# reefpi_pico_io.net
KiCad netlist of a schematic drawn in Altium Designer
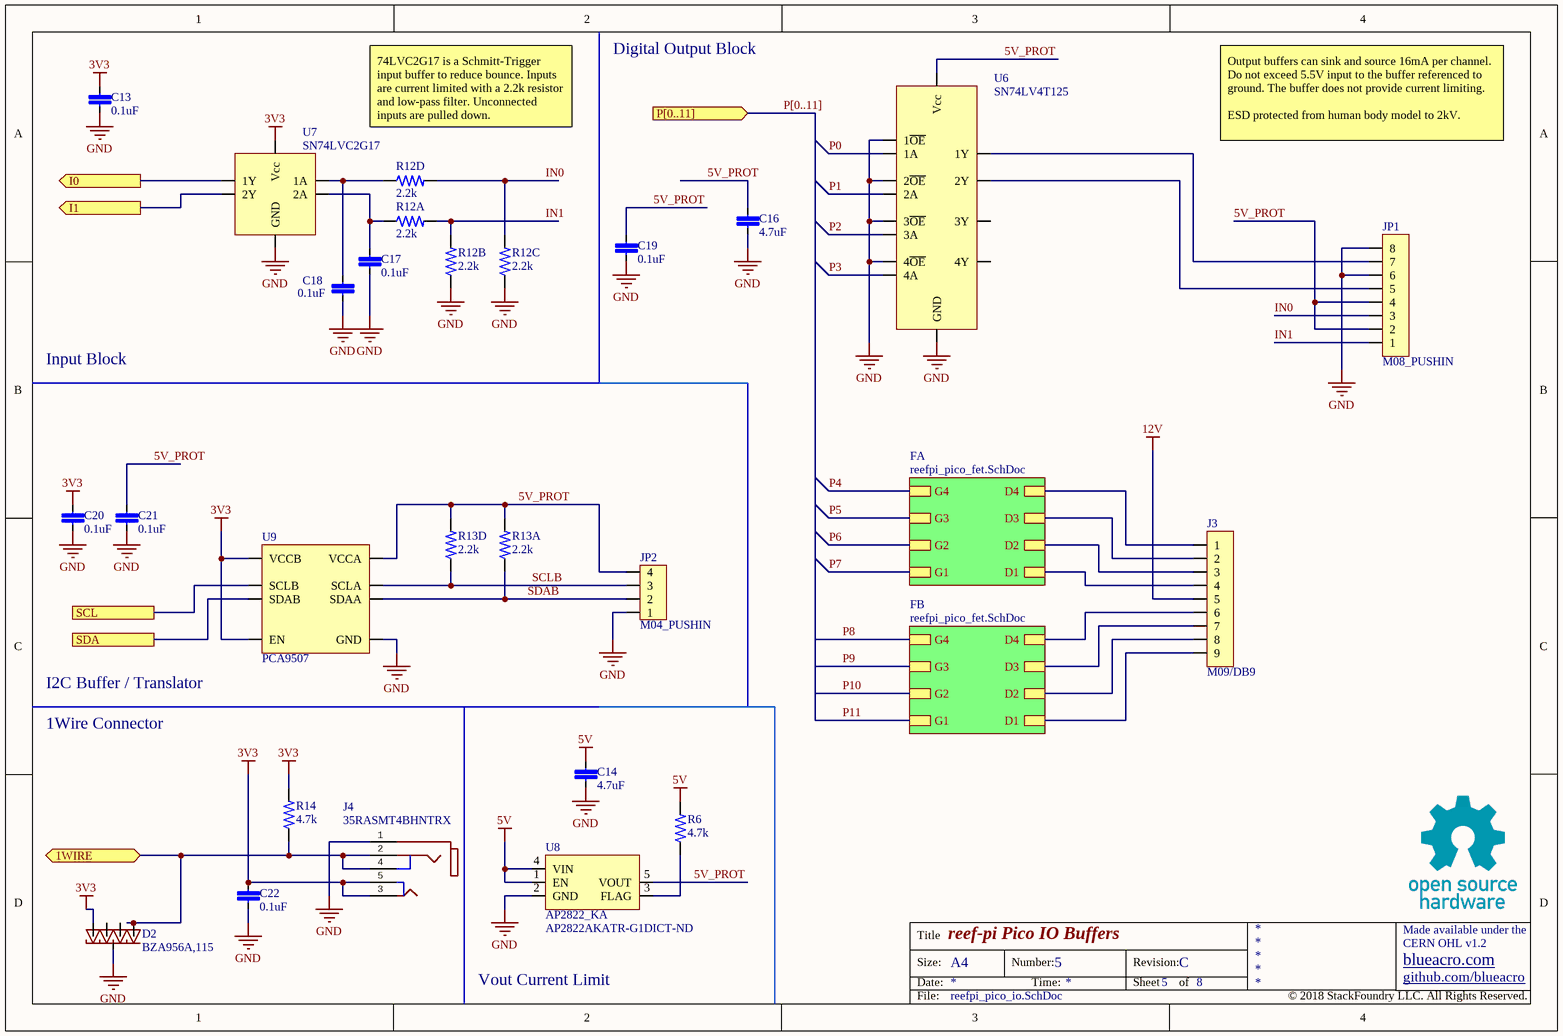
[diagram p0: reefpi_pico_io.SchDoc]

(export (version "E")
  (design (tool "Eeschema 10.0.6"))
  (components
    (comp (ref "C13") (value "0.1uF") (footprint "C0603") (libsource (lib "rcl") (part "C-EU")))
    (comp (ref "C14") (value "4.7uF") (footprint "C1210") (libsource (lib "rcl") (part "C-EU")))
    (comp (ref "C16") (value "4.7uF") (footprint "C1210") (libsource (lib "rcl") (part "C-EU")))
    (comp (ref "C17") (value "0.1uF") (footprint "C0603") (libsource (lib "rcl") (part "C-EU")))
    (comp (ref "C18") (value "0.1uF") (footprint "C0603") (libsource (lib "rcl") (part "C-EU")))
    (comp (ref "C19") (value "0.1uF") (footprint "C0603") (libsource (lib "rcl") (part "C-EU")))
    (comp (ref "C20") (value "0.1uF") (footprint "C0603") (libsource (lib "rcl") (part "C-EU")))
    (comp (ref "C21") (value "0.1uF") (footprint "C0603") (libsource (lib "rcl") (part "C-EU")))
    (comp (ref "C22") (value "0.1uF") (footprint "C0603") (libsource (lib "rcl") (part "C-EU")))
    (comp (ref "D2")
      (value "BZA956A,115")
      (footprint "SOT665")
      (libsource (lib "general") (part "DIODE_TVS_4x"))
    )
    (comp (ref "J3")
      (value "M09/DB9")
      (footprint "D09S33E4GV00LF")
      (libsource (lib "connectors") (part "M09/DB9"))
    )
    (comp (ref "J4")
      (value "35RASMT4BHNTRX")
      (footprint "35RASMT4BHNTRX")
      (libsource (lib "connectors") (part "35RASMT4BHNTRX"))
    )
    (comp (ref "JP1")
      (value "M08_PUSHIN")
      (footprint "PHOENIX_PTSM_8_1778829")
      (libsource (lib "connectors") (part "M08_PUSHIN"))
    )
    (comp (ref "JP2")
      (value "M04_PUSHIN")
      (footprint "PHOENIX_PTSM_4_1814935")
      (libsource (lib "connectors") (part "M04_PUSHIN"))
    )
    (comp (ref "R6") (value "4.7k") (footprint "R0603") (libsource (lib "rcl") (part "R-US")))
    (comp (ref "R12") (value "2.2k") (footprint "R0603x4") (libsource (lib "rcl") (part "R-US-4ch")))
    (comp (ref "R13") (value "2.2k") (footprint "R0603x4") (libsource (lib "rcl") (part "R-US-4ch")))
    (comp (ref "R14") (value "4.7k") (footprint "R0603") (libsource (lib "rcl") (part "R-US")))
    (comp (ref "U6") (value "SN74LV4T125") (footprint "PW14") (libsource (lib "texas") (part "SN74LV4T125")))
    (comp (ref "U7")
      (value "SN74LVC2G17")
      (footprint "SOT23-6")
      (libsource (lib "texas") (part "SN74LVC2G17"))
    )
    (comp (ref "U8")
      (value "AP2822_KA")
      (footprint "SOT23-5L")
      (fields (field (name "SUPPLIER PART NUMBER 1") "AP2822AKATR-G1DICT-ND"))
      (libsource (lib "diodesinc") (part "AP2822_KA"))
    )
    (comp (ref "U9") (value "PCA9507") (footprint "SO-8") (libsource (lib "general") (part "PCA9507")))
  )
  (nets
    (net (code "1") (name "/1WIRE") (class "Default")
      (node (ref "D2") (pin "1") (pinfunction "1_1") (pintype "passive"))
      (node (ref "J4") (pin "2") (pinfunction "MID_2") (pintype "passive"))
      (node (ref "J4") (pin "4") (pinfunction "MID_4") (pintype "passive"))
      (node (ref "R14") (pin "1") (pinfunction "1_1") (pintype "passive"))
    )
    (net (code "2") (name "/5V_PROT") (class "Default")
      (node (ref "C16") (pin "1") (pinfunction "1_1") (pintype "passive"))
      (node (ref "C19") (pin "1") (pinfunction "1_1") (pintype "passive"))
      (node (ref "C21") (pin "1") (pinfunction "1_1") (pintype "passive"))
      (node (ref "JP1") (pin "2") (pinfunction "2_2") (pintype "passive"))
      (node (ref "JP1") (pin "4") (pinfunction "4_4") (pintype "passive"))
      (node (ref "JP2") (pin "4") (pinfunction "4_4") (pintype "passive"))
      (node (ref "R13") (pin "2") (pinfunction "2_2") (pintype "passive"))
      (node (ref "R13") (pin "8") (pinfunction "8_8") (pintype "passive"))
      (node (ref "U6") (pin "14") (pinfunction "Vcc_14") (pintype "passive"))
      (node (ref "U8") (pin "5") (pinfunction "VOUT_5") (pintype "passive"))
      (node (ref "U9") (pin "1") (pinfunction "VCCA_1") (pintype "passive"))
    )
    (net (code "3") (name "/D1") (class "Default")
      (node (ref "J3") (pin "4") (pinfunction "4_4") (pintype "passive"))
    )
    (net (code "4") (name "/D1_1") (class "Default")
      (node (ref "J3") (pin "9") (pinfunction "9_9") (pintype "passive"))
    )
    (net (code "5") (name "/D2") (class "Default")
      (node (ref "J3") (pin "3") (pinfunction "3_3") (pintype "passive"))
    )
    (net (code "6") (name "/D2_1") (class "Default")
      (node (ref "J3") (pin "8") (pinfunction "8_8") (pintype "passive"))
    )
    (net (code "7") (name "/D3") (class "Default")
      (node (ref "J3") (pin "2") (pinfunction "2_2") (pintype "passive"))
    )
    (net (code "8") (name "/D3_1") (class "Default")
      (node (ref "J3") (pin "7") (pinfunction "7_7") (pintype "passive"))
    )
    (net (code "9") (name "/D4") (class "Default")
      (node (ref "J3") (pin "6") (pinfunction "6_6") (pintype "passive"))
    )
    (net (code "10") (name "/D4_1") (class "Default")
      (node (ref "J3") (pin "1") (pinfunction "1_1") (pintype "passive"))
    )
    (net (code "11") (name "/I0") (class "Default")
      (node (ref "U7") (pin "6") (pinfunction "1Y_6") (pintype "passive"))
    )
    (net (code "12") (name "/I1") (class "Default")
      (node (ref "U7") (pin "4") (pinfunction "2Y_4") (pintype "passive"))
    )
    (net (code "13") (name "/IN0") (class "Default")
      (node (ref "JP1") (pin "3") (pinfunction "3_3") (pintype "passive"))
      (node (ref "R12") (pin "6") (pinfunction "6_6") (pintype "passive"))
      (node (ref "R12") (pin "8") (pinfunction "8_8") (pintype "passive"))
    )
    (net (code "14") (name "/IN1") (class "Default")
      (node (ref "JP1") (pin "1") (pinfunction "1_1") (pintype "passive"))
      (node (ref "R12") (pin "2") (pinfunction "2_2") (pintype "passive"))
      (node (ref "R12") (pin "4") (pinfunction "4_4") (pintype "passive"))
    )
    (net (code "15") (name "/P0") (class "Default")
      (node (ref "U6") (pin "2") (pinfunction "1A_2") (pintype "passive"))
    )
    (net (code "16") (name "/P1") (class "Default")
      (node (ref "U6") (pin "5") (pinfunction "2A_5") (pintype "passive"))
    )
    (net (code "17") (name "/P2") (class "Default")
      (node (ref "U6") (pin "9") (pinfunction "3A_9") (pintype "passive"))
    )
    (net (code "18") (name "/P3") (class "Default")
      (node (ref "U6") (pin "12") (pinfunction "4A_12") (pintype "passive"))
    )
    (net (code "28") (name "/SCL") (class "Default")
      (node (ref "U9") (pin "7") (pinfunction "SCLB_7") (pintype "passive"))
    )
    (net (code "29") (name "/SCLB") (class "Default")
      (node (ref "JP2") (pin "3") (pinfunction "3_3") (pintype "passive"))
      (node (ref "R13") (pin "7") (pinfunction "7_7") (pintype "passive"))
      (node (ref "U9") (pin "2") (pinfunction "SCLA_2") (pintype "passive"))
    )
    (net (code "30") (name "/SDA") (class "Default")
      (node (ref "U9") (pin "6") (pinfunction "SDAB_6") (pintype "passive"))
    )
    (net (code "31") (name "/SDAB") (class "Default")
      (node (ref "JP2") (pin "2") (pinfunction "2_2") (pintype "passive"))
      (node (ref "R13") (pin "1") (pinfunction "1_1") (pintype "passive"))
      (node (ref "U9") (pin "3") (pinfunction "SDAA_3") (pintype "passive"))
    )
    (net (code "32") (name "3V3") (class "Default")
      (node (ref "C13") (pin "1") (pinfunction "1_1") (pintype "passive"))
      (node (ref "C20") (pin "1") (pinfunction "1_1") (pintype "passive"))
      (node (ref "C22") (pin "1") (pinfunction "1_1") (pintype "passive"))
      (node (ref "D2") (pin "5") (pinfunction "5_5") (pintype "passive"))
      (node (ref "J4") (pin "3") (pinfunction "TIP_3") (pintype "passive"))
      (node (ref "J4") (pin "5") (pinfunction "MID_5") (pintype "passive"))
      (node (ref "R14") (pin "2") (pinfunction "2_2") (pintype "passive"))
      (node (ref "U7") (pin "5") (pinfunction "Vcc_5") (pintype "passive"))
      (node (ref "U9") (pin "5") (pinfunction "EN_5") (pintype "passive"))
      (node (ref "U9") (pin "8") (pinfunction "VCCB_8") (pintype "passive"))
    )
    (net (code "33") (name "5V") (class "Default")
      (node (ref "C14") (pin "1") (pinfunction "1_1") (pintype "passive"))
      (node (ref "R6") (pin "2") (pinfunction "2_2") (pintype "passive"))
      (node (ref "U8") (pin "1") (pinfunction "EN_1") (pintype "passive"))
      (node (ref "U8") (pin "4") (pinfunction "VIN_4") (pintype "passive"))
    )
    (net (code "34") (name "12V") (class "Default")
      (node (ref "J3") (pin "5") (pinfunction "5_5") (pintype "passive"))
    )
    (net (code "35") (name "GND") (class "Default")
      (node (ref "C13") (pin "2") (pinfunction "2_2") (pintype "passive"))
      (node (ref "C14") (pin "2") (pinfunction "2_2") (pintype "passive"))
      (node (ref "C16") (pin "2") (pinfunction "2_2") (pintype "passive"))
      (node (ref "C17") (pin "2") (pinfunction "2_2") (pintype "passive"))
      (node (ref "C18") (pin "2") (pinfunction "2_2") (pintype "passive"))
      (node (ref "C19") (pin "2") (pinfunction "2_2") (pintype "passive"))
      (node (ref "C20") (pin "2") (pinfunction "2_2") (pintype "passive"))
      (node (ref "C21") (pin "2") (pinfunction "2_2") (pintype "passive"))
      (node (ref "C22") (pin "2") (pinfunction "2_2") (pintype "passive"))
      (node (ref "D2") (pin "2") (pinfunction "2_2") (pintype "passive"))
      (node (ref "J4") (pin "1") (pinfunction "OUTER_1") (pintype "passive"))
      (node (ref "JP1") (pin "6") (pinfunction "6_6") (pintype "passive"))
      (node (ref "JP1") (pin "8") (pinfunction "8_8") (pintype "passive"))
      (node (ref "JP2") (pin "1") (pinfunction "1_1") (pintype "passive"))
      (node (ref "R12") (pin "3") (pinfunction "3_3") (pintype "passive"))
      (node (ref "R12") (pin "5") (pinfunction "5_5") (pintype "passive"))
      (node (ref "U6") (pin "1") (pinfunction "1~{OE}_1") (pintype "passive"))
      (node (ref "U6") (pin "10") (pinfunction "3~{OE}_10") (pintype "passive"))
      (node (ref "U6") (pin "13") (pinfunction "4~{OE}_13") (pintype "passive"))
      (node (ref "U6") (pin "4") (pinfunction "2~{OE}_4") (pintype "passive"))
      (node (ref "U6") (pin "7") (pinfunction "GND_7") (pintype "passive"))
      (node (ref "U7") (pin "2") (pinfunction "GND_2") (pintype "passive"))
      (node (ref "U8") (pin "2") (pinfunction "GND_2") (pintype "passive"))
      (node (ref "U9") (pin "4") (pinfunction "GND_4") (pintype "passive"))
    )
    (net (code "36") (name "Net-(U6-1Y)") (class "Default")
      (node (ref "JP1") (pin "7") (pinfunction "7_7") (pintype "passive"))
      (node (ref "U6") (pin "3") (pinfunction "1Y_3") (pintype "passive"))
    )
    (net (code "37") (name "Net-(U6-2Y)") (class "Default")
      (node (ref "JP1") (pin "5") (pinfunction "5_5") (pintype "passive"))
      (node (ref "U6") (pin "6") (pinfunction "2Y_6") (pintype "passive"))
    )
    (net (code "38") (name "Net-(U7-1A)") (class "Default")
      (node (ref "C18") (pin "1") (pinfunction "1_1") (pintype "passive"))
      (node (ref "R12") (pin "7") (pinfunction "7_7") (pintype "passive"))
      (node (ref "U7") (pin "1") (pinfunction "1A_1") (pintype "passive"))
    )
    (net (code "39") (name "Net-(U7-2A)") (class "Default")
      (node (ref "C17") (pin "1") (pinfunction "1_1") (pintype "passive"))
      (node (ref "R12") (pin "1") (pinfunction "1_1") (pintype "passive"))
      (node (ref "U7") (pin "3") (pinfunction "2A_3") (pintype "passive"))
    )
    (net (code "40") (name "Net-(U8-FLAG)") (class "Default")
      (node (ref "R6") (pin "1") (pinfunction "1_1") (pintype "passive"))
      (node (ref "U8") (pin "3") (pinfunction "FLAG_3") (pintype "passive"))
    )
    (net (code "41") (name "unconnected-(D2-Pad3)") (class "Default")
      (node (ref "D2") (pin "3") (pinfunction "3_3") (pintype "passive"))
    )
    (net (code "42") (name "unconnected-(D2-Pad4)") (class "Default")
      (node (ref "D2") (pin "4") (pinfunction "4_4") (pintype "passive"))
    )
    (net (code "43") (name "unconnected-(U6-3Y-Pad8)") (class "Default")
      (node (ref "U6") (pin "8") (pinfunction "3Y_8") (pintype "passive"))
    )
    (net (code "44") (name "unconnected-(U6-4Y-Pad11)") (class "Default")
      (node (ref "U6") (pin "11") (pinfunction "4Y_11") (pintype "passive"))
    )
  )
)
